# STM32F407VG-F.net
KiCad netlist of a schematic drawn in Altium Designer
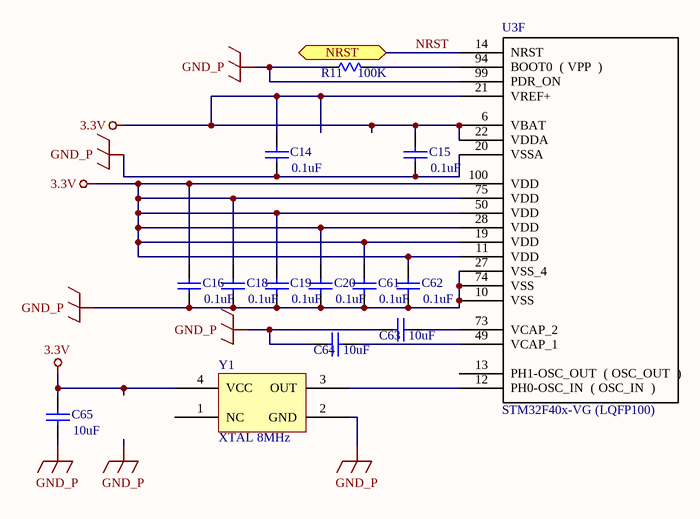
[diagram p0: STM32F407VG-F.SchDoc]

(export (version "E")
  (design (tool "Eeschema 10.0.6"))
  (components
    (comp (ref "C14")
      (value "0.1uF")
      (footprint "C0603-S")
      (description "Capacitor")
      (fields (field (name "PUBLISHER") "Altium Limited"))
      (libsource (lib "Miscellaneous Devices") (part "Cap"))
    )
    (comp (ref "C15")
      (value "0.1uF")
      (footprint "C0603-S")
      (description "Capacitor")
      (fields (field (name "PUBLISHER") "Altium Limited"))
      (libsource (lib "Miscellaneous Devices") (part "Cap"))
    )
    (comp (ref "C16")
      (value "0.1uF")
      (footprint "C0603-S")
      (description "Capacitor")
      (fields (field (name "PUBLISHER") "Altium Limited"))
      (libsource (lib "Miscellaneous Devices") (part "Cap"))
    )
    (comp (ref "C18")
      (value "0.1uF")
      (footprint "C0603-S")
      (description "Capacitor")
      (fields (field (name "PUBLISHER") "Altium Limited"))
      (libsource (lib "Miscellaneous Devices") (part "Cap"))
    )
    (comp (ref "C19")
      (value "0.1uF")
      (footprint "C0603-S")
      (description "Capacitor")
      (fields (field (name "PUBLISHER") "Altium Limited"))
      (libsource (lib "Miscellaneous Devices") (part "Cap"))
    )
    (comp (ref "C20")
      (value "0.1uF")
      (footprint "C0603-S")
      (description "Capacitor")
      (fields (field (name "PUBLISHER") "Altium Limited"))
      (libsource (lib "Miscellaneous Devices") (part "Cap"))
    )
    (comp (ref "C61")
      (value "0.1uF")
      (footprint "C0603-S")
      (description "Capacitor")
      (fields (field (name "PUBLISHER") "Altium Limited"))
      (libsource (lib "Miscellaneous Devices") (part "Cap"))
    )
    (comp (ref "C62")
      (value "0.1uF")
      (footprint "C0603-S")
      (description "Capacitor")
      (fields (field (name "PUBLISHER") "Altium Limited"))
      (libsource (lib "Miscellaneous Devices") (part "Cap"))
    )
    (comp (ref "C63")
      (value "10uF")
      (footprint "C0603-S")
      (description "Capacitor")
      (fields (field (name "PUBLISHER") "Altium Limited"))
      (libsource (lib "Miscellaneous Devices") (part "Cap"))
    )
    (comp (ref "C64")
      (value "10uF")
      (footprint "C0603-S")
      (description "Capacitor")
      (fields (field (name "PUBLISHER") "Altium Limited"))
      (libsource (lib "Miscellaneous Devices") (part "Cap"))
    )
    (comp (ref "C65")
      (value "10uF")
      (footprint "C0603-S")
      (description "Capacitor")
      (fields (field (name "PUBLISHER") "Altium Limited"))
      (libsource (lib "Miscellaneous Devices") (part "Cap"))
    )
    (comp (ref "R11")
      (value "100K")
      (footprint "R0603-S")
      (description "Resistor")
      (fields (field (name "PUBLISHER") "Altium Limited"))
      (libsource (lib "Temp") (part "Res"))
    )
    (comp (ref "U3")
      (value "STM32F40x-VG (LQFP100)")
      (footprint "LQFP100_N")
      (libsource (lib "Microcontrollers Class") (part "STM32F40x-VG"))
    )
    (comp (ref "Y1")
      (value "XTAL 8MHz")
      (footprint "XTAL 3.3X5.0S-SM")
      (libsource (lib "Mic2805") (part "XTAL"))
    )
  )
  (nets
    (net (code "1") (name "/NRST") (class "Default")
      (node (ref "U3") (pin "14") (pinfunction "NRST_14") (pintype "passive"))
    )
    (net (code "2") (name "3.3V") (class "Default")
      (node (ref "C14") (pin "1") (pinfunction "1_1") (pintype "passive"))
      (node (ref "C15") (pin "1") (pinfunction "1_1") (pintype "passive"))
      (node (ref "C16") (pin "1") (pinfunction "1_1") (pintype "passive"))
      (node (ref "C18") (pin "1") (pinfunction "1_1") (pintype "passive"))
      (node (ref "C19") (pin "1") (pinfunction "1_1") (pintype "passive"))
      (node (ref "C20") (pin "1") (pinfunction "1_1") (pintype "passive"))
      (node (ref "C61") (pin "1") (pinfunction "1_1") (pintype "passive"))
      (node (ref "C62") (pin "1") (pinfunction "1_1") (pintype "passive"))
      (node (ref "C65") (pin "1") (pinfunction "1_1") (pintype "passive"))
      (node (ref "U3") (pin "100") (pinfunction "VDD_100") (pintype "passive"))
      (node (ref "U3") (pin "11") (pinfunction "VDD_11") (pintype "passive"))
      (node (ref "U3") (pin "19") (pinfunction "VDD_19") (pintype "passive"))
      (node (ref "U3") (pin "21") (pinfunction "VREF+_21") (pintype "passive"))
      (node (ref "U3") (pin "22") (pinfunction "VDDA_22") (pintype "passive"))
      (node (ref "U3") (pin "28") (pinfunction "VDD_28") (pintype "passive"))
      (node (ref "U3") (pin "50") (pinfunction "VDD_50") (pintype "passive"))
      (node (ref "U3") (pin "6") (pinfunction "VBAT_6") (pintype "passive"))
      (node (ref "U3") (pin "75") (pinfunction "VDD_75") (pintype "passive"))
      (node (ref "Y1") (pin "4") (pinfunction "VCC_4") (pintype "passive"))
    )
    (net (code "3") (name "GND_P") (class "Default")
      (node (ref "C14") (pin "2") (pinfunction "2_2") (pintype "passive"))
      (node (ref "C15") (pin "2") (pinfunction "2_2") (pintype "passive"))
      (node (ref "C16") (pin "2") (pinfunction "2_2") (pintype "passive"))
      (node (ref "C18") (pin "2") (pinfunction "2_2") (pintype "passive"))
      (node (ref "C19") (pin "2") (pinfunction "2_2") (pintype "passive"))
      (node (ref "C20") (pin "2") (pinfunction "2_2") (pintype "passive"))
      (node (ref "C61") (pin "2") (pinfunction "2_2") (pintype "passive"))
      (node (ref "C62") (pin "2") (pinfunction "2_2") (pintype "passive"))
      (node (ref "C63") (pin "1") (pinfunction "1_1") (pintype "passive"))
      (node (ref "C64") (pin "1") (pinfunction "1_1") (pintype "passive"))
      (node (ref "C65") (pin "2") (pinfunction "2_2") (pintype "passive"))
      (node (ref "R11") (pin "2") (pinfunction "2_2") (pintype "passive"))
      (node (ref "U3") (pin "10") (pinfunction "VSS_10") (pintype "passive"))
      (node (ref "U3") (pin "20") (pinfunction "VSSA_20") (pintype "passive"))
      (node (ref "U3") (pin "27") (pinfunction "VSS_4_27") (pintype "passive"))
      (node (ref "U3") (pin "74") (pinfunction "VSS_74") (pintype "passive"))
      (node (ref "U3") (pin "99") (pinfunction "PDR_ON_99") (pintype "passive"))
      (node (ref "Y1") (pin "2") (pinfunction "GND_2") (pintype "passive"))
    )
    (net (code "4") (name "Net-(U3F-BOOT0__(_VPP__))") (class "Default")
      (node (ref "R11") (pin "1") (pinfunction "1_1") (pintype "passive"))
      (node (ref "U3") (pin "94") (pinfunction "BOOT0__(_VPP__)_94") (pintype "passive"))
    )
    (net (code "5") (name "Net-(U3F-PH0-OSC_IN__(_OSC_IN__))") (class "Default")
      (node (ref "U3") (pin "12") (pinfunction "PH0-OSC_IN__(_OSC_IN__)_12") (pintype "passive"))
      (node (ref "Y1") (pin "3") (pinfunction "OUT_3") (pintype "passive"))
    )
    (net (code "6") (name "Net-(U3F-VCAP_1)") (class "Default")
      (node (ref "C64") (pin "2") (pinfunction "2_2") (pintype "passive"))
      (node (ref "U3") (pin "49") (pinfunction "VCAP_1_49") (pintype "passive"))
    )
    (net (code "7") (name "Net-(U3F-VCAP_2)") (class "Default")
      (node (ref "C63") (pin "2") (pinfunction "2_2") (pintype "passive"))
      (node (ref "U3") (pin "73") (pinfunction "VCAP_2_73") (pintype "passive"))
    )
    (net (code "8") (name "unconnected-(U3F-PH1-OSC_OUT__(_OSC_OUT__)-Pad13)") (class "Default")
      (node (ref "U3") (pin "13") (pinfunction "PH1-OSC_OUT__(_OSC_OUT__)_13") (pintype "passive"))
    )
    (net (code "9") (name "unconnected-(Y1-NC-Pad1)") (class "Default")
      (node (ref "Y1") (pin "1") (pinfunction "NC_1") (pintype "passive"))
    )
  )
)
